# Energieversorgung.net
KiCad netlist of a schematic drawn in Altium Designer
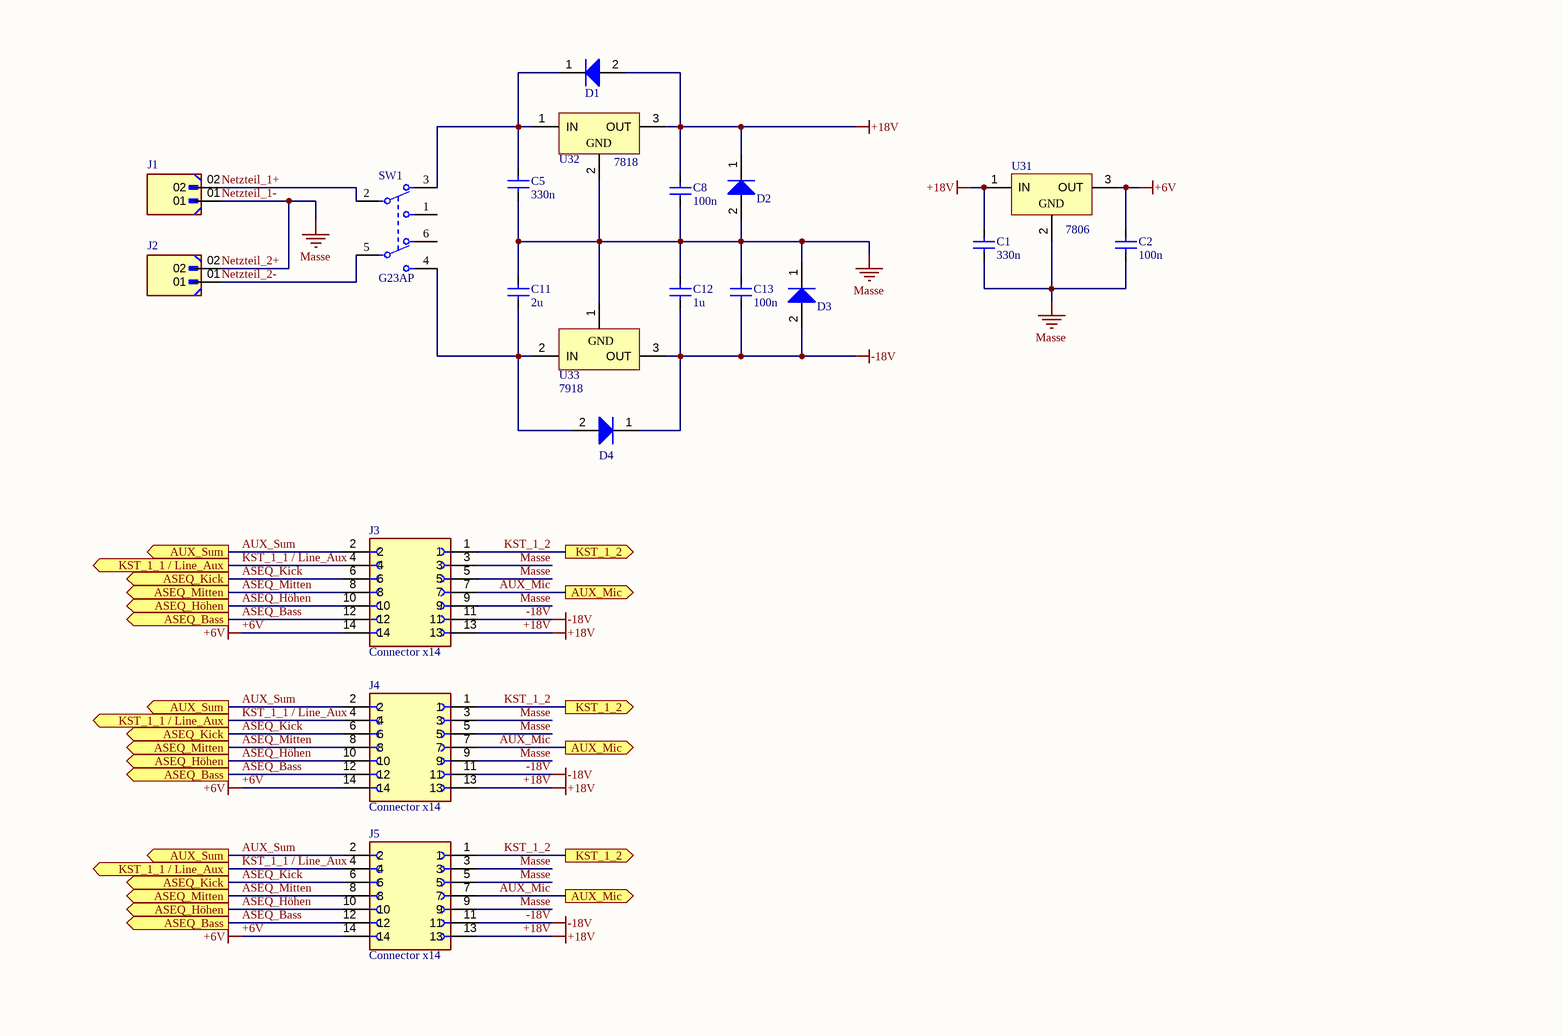
[diagram p0: Energieversorgung.SchDoc]

(export (version "E")
  (design (tool "Eeschema 10.0.6"))
  (components
    (comp (ref "C1")
      (value "330n")
      (footprint "0805")
      (description "0805 Kondensator")
      (libsource (lib "Bauteile") (part "0805 Kondensator"))
    )
    (comp (ref "C2")
      (value "100n")
      (footprint "0805")
      (description "0805 Kondensator")
      (libsource (lib "Bauteile") (part "0805 Kondensator"))
    )
    (comp (ref "C5")
      (value "330n")
      (footprint "0805")
      (description "0805 Kondensator")
      (libsource (lib "Bauteile") (part "0805 Kondensator"))
    )
    (comp (ref "C8")
      (value "100n")
      (footprint "0805")
      (description "0805 Kondensator")
      (libsource (lib "Bauteile") (part "0805 Kondensator"))
    )
    (comp (ref "C11")
      (value "2u")
      (footprint "0805")
      (description "0805 Kondensator")
      (libsource (lib "Bauteile") (part "0805 Kondensator"))
    )
    (comp (ref "C12")
      (value "1u")
      (footprint "0805")
      (description "0805 Kondensator")
      (libsource (lib "Bauteile") (part "0805 Kondensator"))
    )
    (comp (ref "C13")
      (value "100n")
      (footprint "0805")
      (description "0805 Kondensator")
      (libsource (lib "Bauteile") (part "0805 Kondensator"))
    )
    (comp (ref "D1")
      (value "1N4001 Diode")
      (footprint "1N4001 Diode")
      (description "Standard Recovery Rectifier, 2-Pin Axial_Lead, Pb-Free, Bulk Bag")
      (fields (field (name "PARTNUMBER") "1N4001") (field (name "MANUFACTURER") "On Semiconductor"))
      (libsource (lib "Bauteile") (part "1N4001 Diode"))
    )
    (comp (ref "D2")
      (value "1N4001 Diode")
      (footprint "1N4001 Diode")
      (description "Standard Recovery Rectifier, 2-Pin Axial_Lead, Pb-Free, Bulk Bag")
      (fields (field (name "PARTNUMBER") "1N4001") (field (name "MANUFACTURER") "On Semiconductor"))
      (libsource (lib "Bauteile") (part "1N4001 Diode"))
    )
    (comp (ref "D3")
      (value "1N4001 Diode")
      (footprint "1N4001 Diode")
      (description "Standard Recovery Rectifier, 2-Pin Axial_Lead, Pb-Free, Bulk Bag")
      (fields (field (name "PARTNUMBER") "1N4001") (field (name "MANUFACTURER") "On Semiconductor"))
      (libsource (lib "Bauteile") (part "1N4001 Diode"))
    )
    (comp (ref "D4")
      (value "1N4001 Diode")
      (footprint "1N4001 Diode")
      (description "Standard Recovery Rectifier, 2-Pin Axial_Lead, Pb-Free, Bulk Bag")
      (fields (field (name "PARTNUMBER") "1N4001") (field (name "MANUFACTURER") "On Semiconductor"))
      (libsource (lib "Bauteile") (part "1N4001 Diode"))
    )
    (comp (ref "J1")
      (value "Connector x2")
      (footprint "Connector x2")
      (description "Connector Header Through Hole 2 position 0.100 (2.54mm)")
      (fields (field (name "MF") "Wurth Elektronik") (field (name "MP") "61300211121"))
      (libsource (lib "Bauteile") (part "Connector x2"))
    )
    (comp (ref "J2")
      (value "Connector x2")
      (footprint "Connector x2")
      (description "Connector Header Through Hole 2 position 0.100 (2.54mm)")
      (fields (field (name "MF") "Wurth Elektronik") (field (name "MP") "61300211121"))
      (libsource (lib "Bauteile") (part "Connector x2"))
    )
    (comp (ref "J3")
      (value "Connector x14")
      (footprint "Connector x14")
      (description "14 Position Header Connector Through Hole")
      (fields (field (name "MF") "Sullins Connector") (field (name "MP") "SFH11-PBPC-D07-ST-BK"))
      (libsource (lib "Bauteile") (part "Connector x14"))
    )
    (comp (ref "J4")
      (value "Connector x14")
      (footprint "Connector x14")
      (description "14 Position Header Connector Through Hole")
      (fields (field (name "MF") "Sullins Connector") (field (name "MP") "SFH11-PBPC-D07-ST-BK"))
      (libsource (lib "Bauteile") (part "Connector x14"))
    )
    (comp (ref "J5")
      (value "Connector x14")
      (footprint "Connector x14")
      (description "14 Position Header Connector Through Hole")
      (fields (field (name "MF") "Sullins Connector") (field (name "MP") "SFH11-PBPC-D07-ST-BK"))
      (libsource (lib "Bauteile") (part "Connector x14"))
    )
    (comp (ref "SW1")
      (value "G23AP")
      (footprint "Connector x4")
      (description "SWITCH TOGGLE DPDT 0.4VA 28V")
      (libsource (lib "Bauteile") (part "Schalter 2x3"))
    )
    (comp (ref "U31")
      (value "7806")
      (footprint "TO220 Spannungsregler 78xx")
      (description "Voltage Regulator, 3-Pin TO-220")
      (libsource (lib "Bauteile") (part "TO 220 Spannungsregler 78xx"))
    )
    (comp (ref "U32")
      (value "7818")
      (footprint "TO220 Spannungsregler 78xx")
      (description "Voltage Regulator, 3-Pin TO-220")
      (libsource (lib "Bauteile") (part "TO 220 Spannungsregler 78xx"))
    )
    (comp (ref "U33")
      (value "7918")
      (footprint "TO220 Spannungsregler 79xx")
      (description "Voltage Regulator, 3-Pin TO-220")
      (libsource (lib "Bauteile") (part "TO 220 Spannungsregler 79xx"))
    )
  )
  (nets
    (net (code "1") (name "+6V") (class "Default")
      (node (ref "C2") (pin "2") (pinfunction "2_2") (pintype "passive"))
      (node (ref "J3") (pin "14") (pinfunction "14_14") (pintype "passive"))
      (node (ref "J4") (pin "14") (pinfunction "14_14") (pintype "passive"))
      (node (ref "J5") (pin "14") (pinfunction "14_14") (pintype "passive"))
      (node (ref "U31") (pin "3") (pinfunction "OUT_3") (pintype "power_in"))
    )
    (net (code "2") (name "+18V") (class "Default")
      (node (ref "C1") (pin "2") (pinfunction "2_2") (pintype "passive"))
      (node (ref "C8") (pin "2") (pinfunction "2_2") (pintype "passive"))
      (node (ref "D1") (pin "2") (pinfunction "A_2") (pintype "passive"))
      (node (ref "D2") (pin "1") (pinfunction "K_1") (pintype "passive"))
      (node (ref "J3") (pin "13") (pinfunction "13_13") (pintype "passive"))
      (node (ref "J4") (pin "13") (pinfunction "13_13") (pintype "passive"))
      (node (ref "J5") (pin "13") (pinfunction "13_13") (pintype "passive"))
      (node (ref "U31") (pin "1") (pinfunction "IN_1") (pintype "passive"))
      (node (ref "U32") (pin "3") (pinfunction "OUT_3") (pintype "power_in"))
    )
    (net (code "3") (name "-18V") (class "Default")
      (node (ref "C12") (pin "2") (pinfunction "2_2") (pintype "passive"))
      (node (ref "C13") (pin "1") (pinfunction "1_1") (pintype "passive"))
      (node (ref "D3") (pin "2") (pinfunction "A_2") (pintype "passive"))
      (node (ref "D4") (pin "1") (pinfunction "K_1") (pintype "passive"))
      (node (ref "J3") (pin "11") (pinfunction "11_11") (pintype "passive"))
      (node (ref "J4") (pin "11") (pinfunction "11_11") (pintype "passive"))
      (node (ref "J5") (pin "11") (pinfunction "11_11") (pintype "passive"))
      (node (ref "U33") (pin "3") (pinfunction "OUT_3") (pintype "power_in"))
    )
    (net (code "4") (name "/ASEQ_Bass") (class "Default")
      (node (ref "J3") (pin "12") (pinfunction "12_12") (pintype "passive"))
      (node (ref "J4") (pin "12") (pinfunction "12_12") (pintype "passive"))
      (node (ref "J5") (pin "12") (pinfunction "12_12") (pintype "passive"))
    )
    (net (code "5") (name "/ASEQ_Höhen") (class "Default")
      (node (ref "J3") (pin "10") (pinfunction "10_10") (pintype "passive"))
      (node (ref "J4") (pin "10") (pinfunction "10_10") (pintype "passive"))
      (node (ref "J5") (pin "10") (pinfunction "10_10") (pintype "passive"))
    )
    (net (code "6") (name "/ASEQ_Kick") (class "Default")
      (node (ref "J3") (pin "6") (pinfunction "6_6") (pintype "passive"))
      (node (ref "J4") (pin "6") (pinfunction "6_6") (pintype "passive"))
      (node (ref "J5") (pin "6") (pinfunction "6_6") (pintype "passive"))
    )
    (net (code "7") (name "/ASEQ_Mitten") (class "Default")
      (node (ref "J3") (pin "8") (pinfunction "8_8") (pintype "passive"))
      (node (ref "J4") (pin "8") (pinfunction "8_8") (pintype "passive"))
      (node (ref "J5") (pin "8") (pinfunction "8_8") (pintype "passive"))
    )
    (net (code "8") (name "/AUX_Mic") (class "Default")
      (node (ref "J3") (pin "7") (pinfunction "7_7") (pintype "passive"))
      (node (ref "J4") (pin "7") (pinfunction "7_7") (pintype "passive"))
      (node (ref "J5") (pin "7") (pinfunction "7_7") (pintype "passive"))
    )
    (net (code "9") (name "/AUX_Sum") (class "Default")
      (node (ref "J3") (pin "2") (pinfunction "2_2") (pintype "passive"))
      (node (ref "J4") (pin "2") (pinfunction "2_2") (pintype "passive"))
      (node (ref "J5") (pin "2") (pinfunction "2_2") (pintype "passive"))
    )
    (net (code "10") (name "/KST_1_1 {slash} Line_Aux") (class "Default")
      (node (ref "J3") (pin "4") (pinfunction "4_4") (pintype "passive"))
      (node (ref "J4") (pin "4") (pinfunction "4_4") (pintype "passive"))
      (node (ref "J5") (pin "4") (pinfunction "4_4") (pintype "passive"))
    )
    (net (code "11") (name "/KST_1_2") (class "Default")
      (node (ref "J3") (pin "1") (pinfunction "1_1") (pintype "passive"))
      (node (ref "J4") (pin "1") (pinfunction "1_1") (pintype "passive"))
      (node (ref "J5") (pin "1") (pinfunction "1_1") (pintype "passive"))
    )
    (net (code "12") (name "/Netzteil_1+") (class "Default")
      (node (ref "J1") (pin "02") (pinfunction "02_02") (pintype "passive"))
      (node (ref "SW1") (pin "2") (pinfunction "2_2") (pintype "passive"))
    )
    (net (code "13") (name "/Netzteil_2-") (class "Default")
      (node (ref "J2") (pin "01") (pinfunction "01_01") (pintype "passive"))
      (node (ref "SW1") (pin "5") (pinfunction "5_5") (pintype "passive"))
    )
    (net (code "14") (name "Masse") (class "Default")
      (node (ref "C1") (pin "1") (pinfunction "1_1") (pintype "passive"))
      (node (ref "C11") (pin "1") (pinfunction "1_1") (pintype "passive"))
      (node (ref "C12") (pin "1") (pinfunction "1_1") (pintype "passive"))
      (node (ref "C13") (pin "2") (pinfunction "2_2") (pintype "passive"))
      (node (ref "C2") (pin "1") (pinfunction "1_1") (pintype "passive"))
      (node (ref "C5") (pin "1") (pinfunction "1_1") (pintype "passive"))
      (node (ref "C8") (pin "1") (pinfunction "1_1") (pintype "passive"))
      (node (ref "D2") (pin "2") (pinfunction "A_2") (pintype "passive"))
      (node (ref "D3") (pin "1") (pinfunction "K_1") (pintype "passive"))
      (node (ref "J1") (pin "01") (pinfunction "01_01") (pintype "passive"))
      (node (ref "J2") (pin "02") (pinfunction "02_02") (pintype "passive"))
      (node (ref "J3") (pin "3") (pinfunction "3_3") (pintype "passive"))
      (node (ref "J3") (pin "5") (pinfunction "5_5") (pintype "passive"))
      (node (ref "J3") (pin "9") (pinfunction "9_9") (pintype "passive"))
      (node (ref "J4") (pin "3") (pinfunction "3_3") (pintype "passive"))
      (node (ref "J4") (pin "5") (pinfunction "5_5") (pintype "passive"))
      (node (ref "J4") (pin "9") (pinfunction "9_9") (pintype "passive"))
      (node (ref "J5") (pin "3") (pinfunction "3_3") (pintype "passive"))
      (node (ref "J5") (pin "5") (pinfunction "5_5") (pintype "passive"))
      (node (ref "J5") (pin "9") (pinfunction "9_9") (pintype "passive"))
      (node (ref "U31") (pin "2") (pinfunction "GND_2") (pintype "power_in"))
      (node (ref "U32") (pin "2") (pinfunction "GND_2") (pintype "power_in"))
      (node (ref "U33") (pin "1") (pinfunction "GND_1") (pintype "power_in"))
    )
    (net (code "15") (name "Net-(D1-K)") (class "Default")
      (node (ref "C5") (pin "2") (pinfunction "2_2") (pintype "passive"))
      (node (ref "D1") (pin "1") (pinfunction "K_1") (pintype "passive"))
      (node (ref "SW1") (pin "3") (pinfunction "3_3") (pintype "passive"))
      (node (ref "U32") (pin "1") (pinfunction "IN_1") (pintype "passive"))
    )
    (net (code "16") (name "Net-(D4-A)") (class "Default")
      (node (ref "C11") (pin "2") (pinfunction "2_2") (pintype "passive"))
      (node (ref "D4") (pin "2") (pinfunction "A_2") (pintype "passive"))
      (node (ref "SW1") (pin "4") (pinfunction "4_4") (pintype "passive"))
      (node (ref "U33") (pin "2") (pinfunction "IN_2") (pintype "passive"))
    )
    (net (code "17") (name "unconnected-(SW1-Pad1)") (class "Default")
      (node (ref "SW1") (pin "1") (pinfunction "1_1") (pintype "passive"))
    )
    (net (code "18") (name "unconnected-(SW1-Pad6)") (class "Default")
      (node (ref "SW1") (pin "6") (pinfunction "6_6") (pintype "passive"))
    )
  )
)
